# MCU_and_Peripherals.net
KiCad netlist of a schematic drawn in Altium Designer
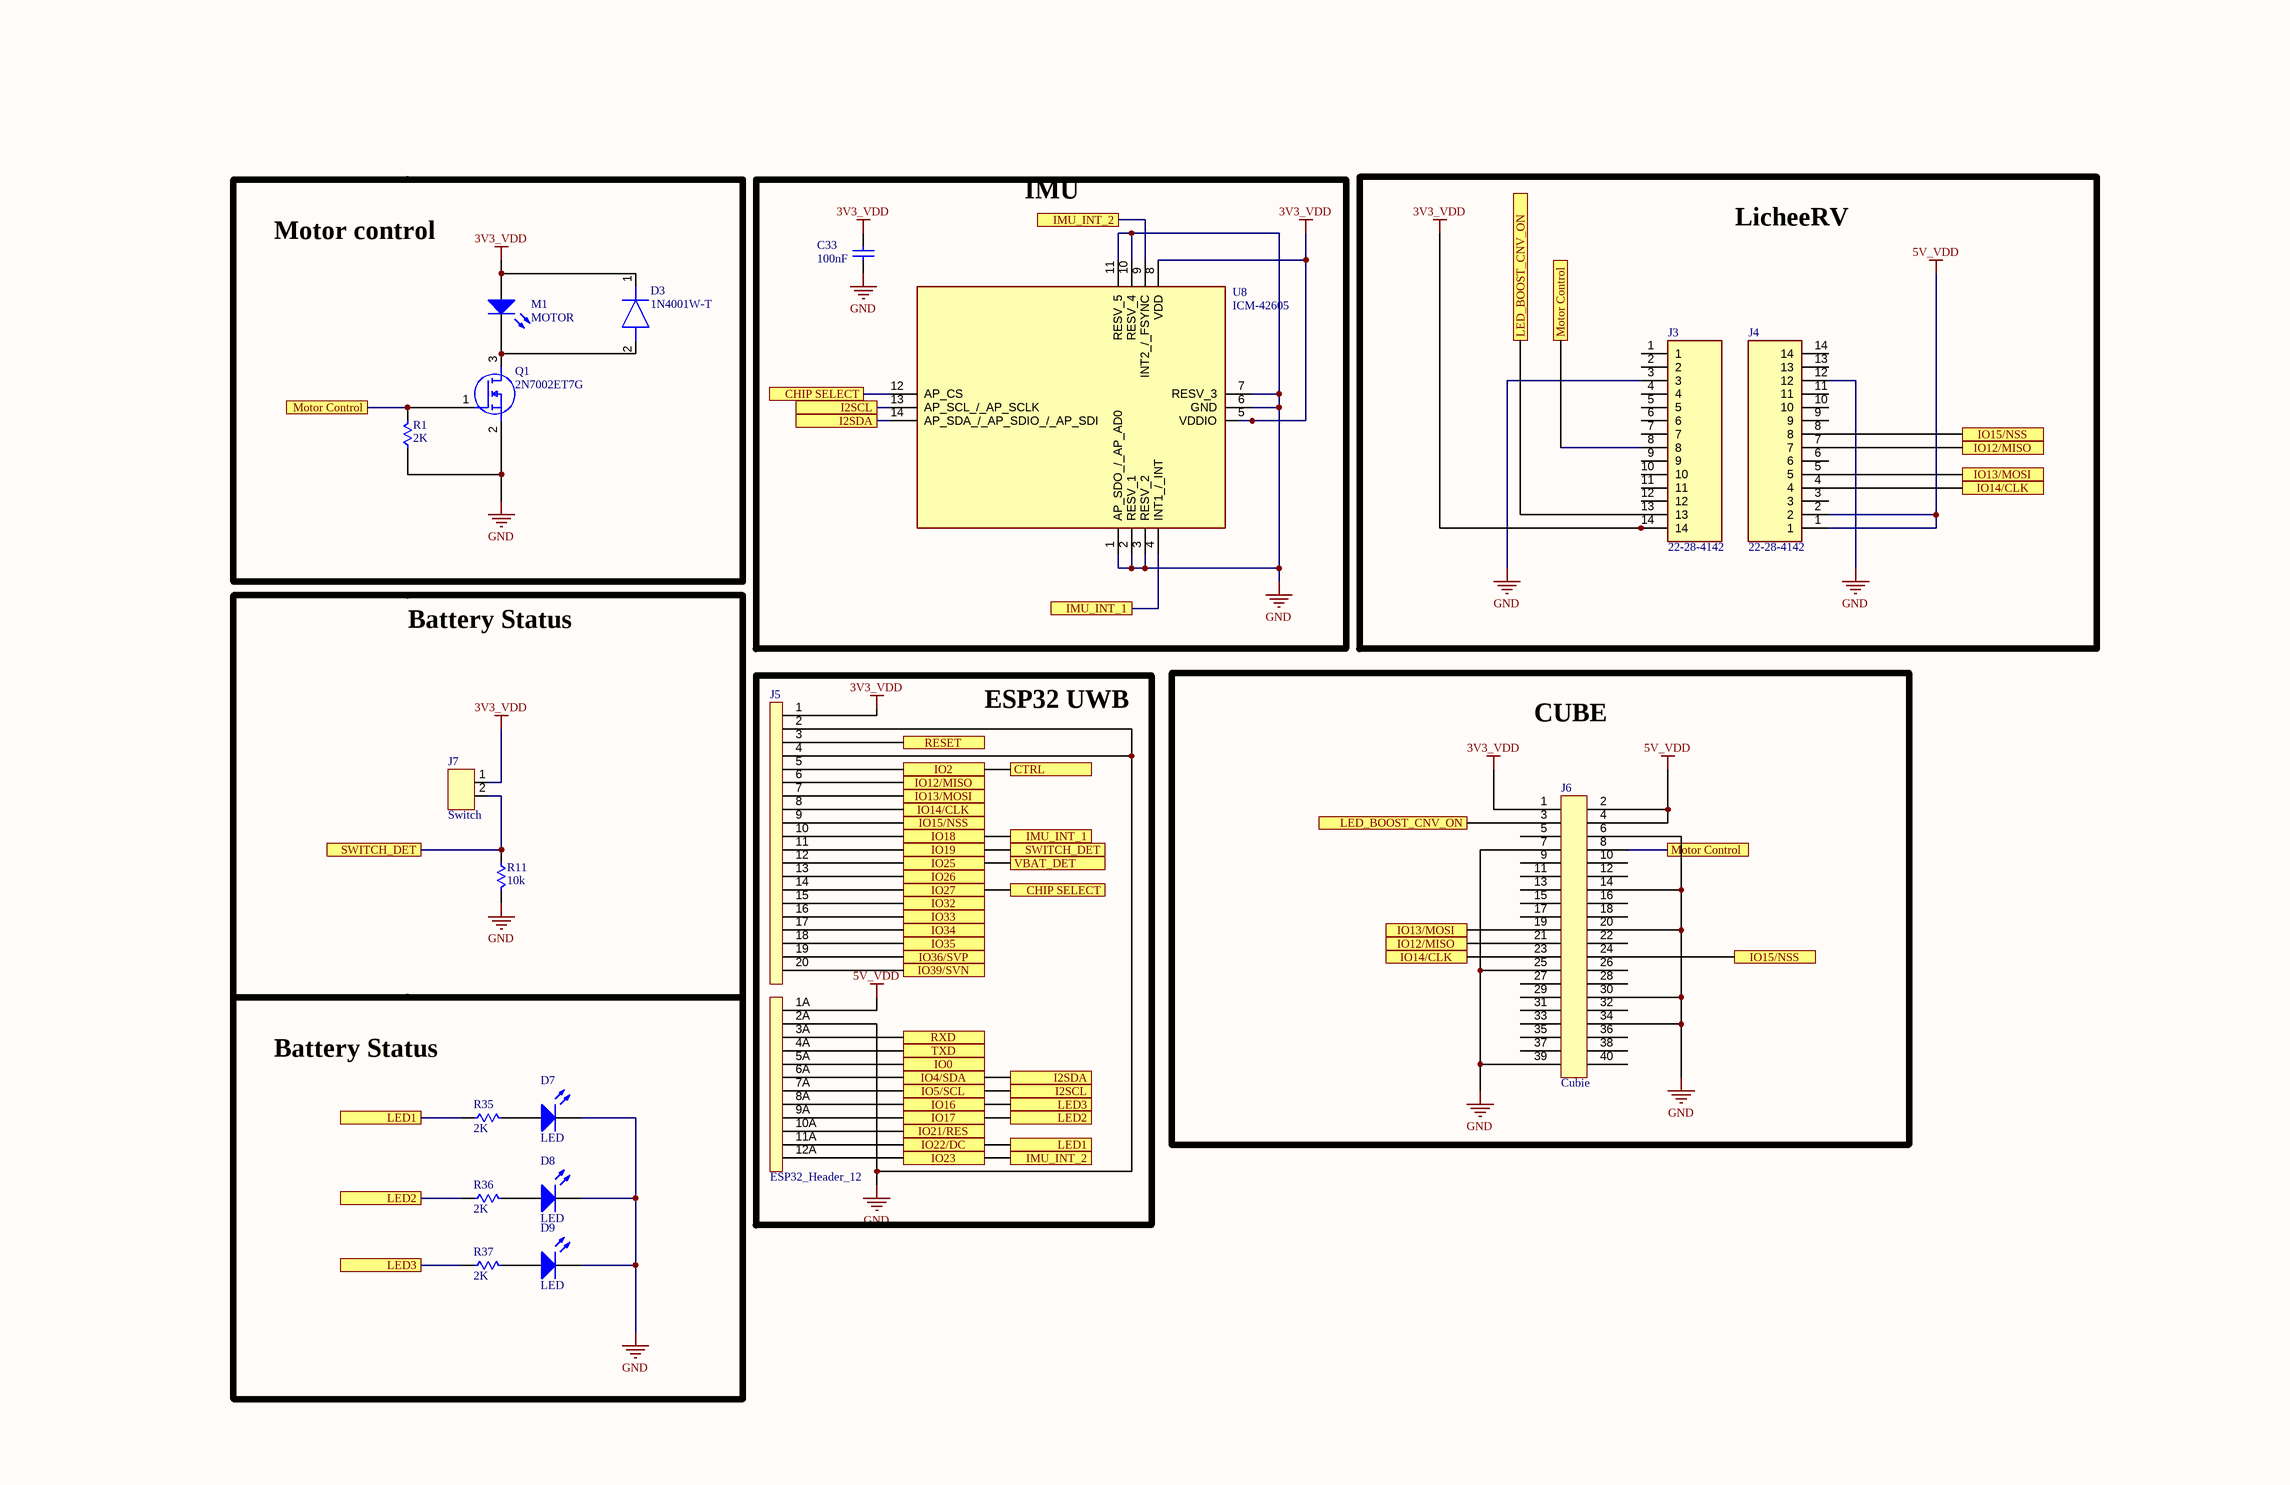
[diagram p0: MCU and Peripherals.SchDoc]

(export (version "E")
  (design (tool "Eeschema 10.0.6"))
  (components
    (comp (ref "C33")
      (value "Capacitor")
      (footprint "0603C")
      (description "Cap Ceramic 0.1uF 50VDC X7R 10% SMD 0603 Paper T/R")
      (fields
        (field (name "MANUFACTURER") "Samsung")
        (field (name "MANUFACTURER PART NUMBER") "CL10B104KB8NNNC")
        (field (name "CAPACITANCE") "100nF")
      )
      (libsource (lib "Altium_Library") (part "Capacitor"))
    )
    (comp (ref "D3")
      (value "1N4001W-T")
      (footprint "SODFL3818X130N")
      (description "Diode")
      (fields (field (name "MOUSER PART NUMBER") "583-1N4001W-T"))
      (libsource (lib "*") (part "1N4001W-T"))
    )
    (comp (ref "D7")
      (value "LED")
      (footprint "PcbLib1:SolderWires")
      (libsource (lib "Schlib1") (part "LED3"))
    )
    (comp (ref "D8")
      (value "LED")
      (footprint "PcbLib1:SolderWires")
      (libsource (lib "Schlib1") (part "LED3"))
    )
    (comp (ref "D9")
      (value "LED")
      (footprint "PcbLib1:SolderWires")
      (libsource (lib "Schlib1") (part "LED3"))
    )
    (comp (ref "J3")
      (value "22-28-4142")
      (footprint "PcbLib1:HDRV14W63P0X254_1X14_3556X250X950P")
      (description "Connector")
      (libsource (lib "*") (part "1-826629-4"))
    )
    (comp (ref "J4")
      (value "22-28-4142")
      (footprint "PcbLib1:HDRV14W63P0X254_1X14_3556X250X950P")
      (description "Connector")
      (libsource (lib "") (part "1-826629-4_1"))
    )
    (comp (ref "J5")
      (value "ESP32_Header_12")
      (footprint "12P-2.54")
      (libsource (lib "Schlib1") (part "ESP32_Header_12"))
    )
    (comp (ref "J6") (value "Cubie") (footprint "40Pin") (libsource (lib "Schlib1") (part "Cubie")))
    (comp (ref "J7") (value "Switch") (footprint "SWITCH SOLDER") (libsource (lib "Schlib1") (part "Switch")))
    (comp (ref "M1")
      (value "MOTOR")
      (footprint "PcbLib1:SolderWires")
      (description "LED")
      (libsource (lib "Schlib1") (part "LED3"))
    )
    (comp (ref "Q1")
      (value "2N7002ET7G")
      (footprint "PcbLib1:SOT96P237X111-3N")
      (description "MOSFET (N-Channel)")
      (fields (field (name "MOUSER PART NUMBER") "863-2N7002ET7G"))
      (libsource (lib "*") (part "2N7002ET7G"))
    )
    (comp (ref "R1")
      (value "2K")
      (footprint "PcbLib1:R0603")
      (description "RES SMD 2K OHM 1% 1/10W 0603")
      (fields
        (field (name "MANUFACTURER") "Yageo")
        (field (name "MANUFACTURER PART NUMBER") "RC0603FR-072KL")
      )
      (libsource (lib "Sunbull_V1R0") (part "RC0603FR-072KL"))
    )
    (comp (ref "R11")
      (value "10k")
      (footprint "PcbLib1:R0603")
      (fields
        (field (name "MANUFACTURER PART NUMBER") "RK73H1JTTD1002F")
        (field (name "TOLERANCE") "±1%")
        (field (name "MOUSER PART NUMBER") "603-RC0603FR-072KL")
      )
      (libsource (lib "Sunbull_V1R0") (part "RC0603FR-072KL"))
    )
    (comp (ref "R35")
      (value "2K")
      (footprint "PcbLib1:R0603")
      (description "RES SMD 2K OHM 1% 1/10W 0603")
      (fields
        (field (name "MANUFACTURER") "Yageo")
        (field (name "MANUFACTURER PART NUMBER") "RC0603FR-072KL")
      )
      (libsource (lib "Sunbull_V1R0") (part "RC0603FR-072KL"))
    )
    (comp (ref "R36")
      (value "2K")
      (footprint "PcbLib1:R0603")
      (description "RES SMD 2K OHM 1% 1/10W 0603")
      (fields
        (field (name "MANUFACTURER") "Yageo")
        (field (name "MANUFACTURER PART NUMBER") "RC0603FR-072KL")
      )
      (libsource (lib "Sunbull_V1R0") (part "RC0603FR-072KL"))
    )
    (comp (ref "R37")
      (value "2K")
      (footprint "PcbLib1:R0603")
      (description "RES SMD 2K OHM 1% 1/10W 0603")
      (fields
        (field (name "MANUFACTURER") "Yageo")
        (field (name "MANUFACTURER PART NUMBER") "RC0603FR-072KL")
      )
      (libsource (lib "Sunbull_V1R0") (part "RC0603FR-072KL"))
    )
    (comp (ref "U8")
      (value "ICM-42605")
      (footprint "PcbLib1:IIM42352")
      (description "Accelerometer")
      (fields (field (name "MOUSER PART NUMBER") "410-ICM-42605"))
      (libsource (lib "*") (part "ICM-42605"))
    )
  )
  (nets
    (net (code "1") (name "/CHIP SELECT") (class "Default")
      (node (ref "J5") (pin "14") (pintype "passive"))
      (node (ref "U8") (pin "12") (pinfunction "AP_CS_12") (pintype "passive"))
    )
    (net (code "2") (name "/CTRL") (class "Default") (node (ref "J5") (pin "5") (pintype "passive")))
    (net (code "3") (name "/I2SCL") (class "Default")
      (node (ref "J5") (pin "7A") (pintype "passive"))
      (node (ref "U8") (pin "13") (pinfunction "AP_SCL_/_AP_SCLK_13") (pintype "passive"))
    )
    (net (code "4") (name "/I2SDA") (class "Default")
      (node (ref "J5") (pin "6A") (pintype "passive"))
      (node (ref "U8") (pin "14") (pinfunction "AP_SDA_/_AP_SDIO_/_AP_SDI_14") (pintype "passive"))
    )
    (net (code "5") (name "/IMU_INT_1") (class "Default")
      (node (ref "J5") (pin "10") (pintype "passive"))
      (node (ref "U8") (pin "4") (pinfunction "INT1_/_INT_4") (pintype "passive"))
    )
    (net (code "6") (name "/IMU_INT_2") (class "Default")
      (node (ref "J5") (pin "12A") (pintype "passive"))
      (node (ref "U8") (pin "9") (pinfunction "INT2_/_FSYNC_9") (pintype "passive"))
    )
    (net (code "7") (name "/IO0") (class "Default") (node (ref "J5") (pin "5A") (pintype "passive")))
    (net (code "8") (name "/IO12{slash}MISO") (class "Default")
      (node (ref "J4") (pin "7") (pinfunction "7_7") (pintype "passive"))
      (node (ref "J5") (pin "6") (pintype "passive"))
      (node (ref "J6") (pin "21") (pinfunction "21_21") (pintype "passive"))
    )
    (net (code "9") (name "/IO13{slash}MOSI") (class "Default")
      (node (ref "J4") (pin "5") (pinfunction "5_5") (pintype "passive"))
      (node (ref "J5") (pin "7") (pintype "passive"))
      (node (ref "J6") (pin "19") (pinfunction "19_19") (pintype "passive"))
    )
    (net (code "10") (name "/IO14{slash}CLK") (class "Default")
      (node (ref "J4") (pin "4") (pinfunction "4_4") (pintype "passive"))
      (node (ref "J5") (pin "8") (pintype "passive"))
      (node (ref "J6") (pin "23") (pinfunction "23_23") (pintype "passive"))
    )
    (net (code "11") (name "/IO15{slash}NSS") (class "Default")
      (node (ref "J4") (pin "8") (pinfunction "8_8") (pintype "passive"))
      (node (ref "J5") (pin "9") (pintype "passive"))
      (node (ref "J6") (pin "24") (pinfunction "24_24") (pintype "passive"))
    )
    (net (code "12") (name "/IO16") (class "Default")
      (node (ref "J5") (pin "8A") (pintype "passive"))
      (node (ref "R37") (pin "1") (pinfunction "1_1") (pintype "passive"))
    )
    (net (code "13") (name "/IO17") (class "Default")
      (node (ref "J5") (pin "9A") (pintype "passive"))
      (node (ref "R36") (pin "1") (pinfunction "1_1") (pintype "passive"))
    )
    (net (code "14") (name "/IO19") (class "Default")
      (node (ref "J5") (pin "11") (pintype "passive"))
      (node (ref "J7") (pin "2") (pinfunction "2_2") (pintype "passive"))
      (node (ref "R11") (pin "1") (pinfunction "1_1") (pintype "passive"))
    )
    (net (code "15") (name "/IO21{slash}RES") (class "Default")
      (node (ref "J5") (pin "10A") (pintype "passive"))
    )
    (net (code "16") (name "/IO22{slash}DC") (class "Default")
      (node (ref "J5") (pin "11A") (pintype "passive"))
      (node (ref "R35") (pin "1") (pinfunction "1_1") (pintype "passive"))
    )
    (net (code "17") (name "/IO25") (class "Default") (node (ref "J5") (pin "12") (pintype "passive")))
    (net (code "18") (name "/IO26") (class "Default") (node (ref "J5") (pin "13") (pintype "passive")))
    (net (code "19") (name "/IO32") (class "Default") (node (ref "J5") (pin "15") (pintype "passive")))
    (net (code "20") (name "/IO33") (class "Default") (node (ref "J5") (pin "16") (pintype "passive")))
    (net (code "21") (name "/IO34") (class "Default") (node (ref "J5") (pin "17") (pintype "passive")))
    (net (code "22") (name "/IO35") (class "Default") (node (ref "J5") (pin "18") (pintype "passive")))
    (net (code "23") (name "/IO36{slash}SVP") (class "Default")
      (node (ref "J5") (pin "19") (pintype "passive"))
    )
    (net (code "24") (name "/IO39{slash}SVN") (class "Default")
      (node (ref "J5") (pin "20") (pintype "passive"))
    )
    (net (code "25") (name "/LED_BOOST_CNV_ON") (class "Default")
      (node (ref "J3") (pin "13") (pinfunction "13_13") (pintype "passive"))
      (node (ref "J6") (pin "3") (pinfunction "11_3") (pintype "passive"))
    )
    (net (code "26") (name "/Motor Control") (class "Default")
      (node (ref "J3") (pin "8") (pinfunction "8_8") (pintype "passive"))
      (node (ref "J6") (pin "8") (pinfunction "16_8") (pintype "passive"))
      (node (ref "Q1") (pin "1") (pinfunction "G_1") (pintype "passive"))
      (node (ref "R1") (pin "2") (pinfunction "2_2") (pintype "passive"))
    )
    (net (code "27") (name "/RESET") (class "Default") (node (ref "J5") (pin "3") (pintype "passive")))
    (net (code "28") (name "/RXD") (class "Default") (node (ref "J5") (pin "3A") (pintype "passive")))
    (net (code "29") (name "/TXD") (class "Default") (node (ref "J5") (pin "4A") (pintype "passive")))
    (net (code "30") (name "3V3_VDD") (class "Default")
      (node (ref "C33") (pin "2") (pinfunction "2_2") (pintype "passive"))
      (node (ref "D3") (pin "1") (pinfunction "K_1") (pintype "passive"))
      (node (ref "J3") (pin "14") (pinfunction "14_14") (pintype "passive"))
      (node (ref "J5") (pin "1") (pintype "passive"))
      (node (ref "J6") (pin "1") (pinfunction "9_1") (pintype "passive"))
      (node (ref "J7") (pin "1") (pinfunction "1_1") (pintype "passive"))
      (node (ref "M1") (pin "1") (pinfunction "A_1") (pintype "passive"))
      (node (ref "U8") (pin "5") (pinfunction "VDDIO_5") (pintype "passive"))
      (node (ref "U8") (pin "8") (pinfunction "VDD_8") (pintype "passive"))
    )
    (net (code "31") (name "5V_VDD") (class "Default")
      (node (ref "J4") (pin "1") (pinfunction "1_1") (pintype "passive"))
      (node (ref "J4") (pin "2") (pinfunction "2_2") (pintype "passive"))
      (node (ref "J5") (pin "1A") (pintype "passive"))
      (node (ref "J6") (pin "2") (pinfunction "10_2") (pintype "passive"))
      (node (ref "J6") (pin "4") (pinfunction "12_4") (pintype "passive"))
    )
    (net (code "32") (name "GND") (class "Default")
      (node (ref "C33") (pin "1") (pinfunction "1_1") (pintype "passive"))
      (node (ref "D7") (pin "2") (pinfunction "K_2") (pintype "passive"))
      (node (ref "D8") (pin "2") (pinfunction "K_2") (pintype "passive"))
      (node (ref "D9") (pin "2") (pinfunction "K_2") (pintype "passive"))
      (node (ref "J3") (pin "3") (pinfunction "3_3") (pintype "passive"))
      (node (ref "J4") (pin "12") (pinfunction "12_12") (pintype "passive"))
      (node (ref "J5") (pin "2") (pintype "passive"))
      (node (ref "J5") (pin "2A") (pintype "passive"))
      (node (ref "J5") (pin "4") (pintype "passive"))
      (node (ref "J6") (pin "14") (pinfunction "22_14") (pintype "passive"))
      (node (ref "J6") (pin "20") (pinfunction "20_20") (pintype "passive"))
      (node (ref "J6") (pin "25") (pinfunction "25_25") (pintype "passive"))
      (node (ref "J6") (pin "30") (pinfunction "30_30") (pintype "passive"))
      (node (ref "J6") (pin "34") (pinfunction "34_34") (pintype "passive"))
      (node (ref "J6") (pin "39") (pinfunction "39_39") (pintype "passive"))
      (node (ref "J6") (pin "6") (pinfunction "14_6") (pintype "passive"))
      (node (ref "J6") (pin "7") (pinfunction "15_7") (pintype "passive"))
      (node (ref "Q1") (pin "2") (pinfunction "S_2") (pintype "passive"))
      (node (ref "R1") (pin "1") (pinfunction "1_1") (pintype "passive"))
      (node (ref "R11") (pin "2") (pinfunction "2_2") (pintype "passive"))
      (node (ref "U8") (pin "1") (pinfunction "AP_SDO_/_AP_AD0_1") (pintype "passive"))
      (node (ref "U8") (pin "10") (pinfunction "RESV_4_10") (pintype "passive"))
      (node (ref "U8") (pin "11") (pinfunction "RESV_5_11") (pintype "passive"))
      (node (ref "U8") (pin "2") (pinfunction "RESV_1_2") (pintype "passive"))
      (node (ref "U8") (pin "3") (pinfunction "RESV_2_3") (pintype "passive"))
      (node (ref "U8") (pin "6") (pinfunction "GND_6") (pintype "passive"))
      (node (ref "U8") (pin "7") (pinfunction "RESV_3_7") (pintype "passive"))
    )
    (net (code "33") (name "Net-(D3-A)") (class "Default")
      (node (ref "D3") (pin "2") (pinfunction "A_2") (pintype "passive"))
      (node (ref "M1") (pin "2") (pinfunction "K_2") (pintype "passive"))
      (node (ref "Q1") (pin "3") (pinfunction "D_3") (pintype "passive"))
    )
    (net (code "34") (name "Net-(D7-A)") (class "Default")
      (node (ref "D7") (pin "1") (pinfunction "A_1") (pintype "passive"))
      (node (ref "R35") (pin "2") (pinfunction "2_2") (pintype "passive"))
    )
    (net (code "35") (name "Net-(D8-A)") (class "Default")
      (node (ref "D8") (pin "1") (pinfunction "A_1") (pintype "passive"))
      (node (ref "R36") (pin "2") (pinfunction "2_2") (pintype "passive"))
    )
    (net (code "36") (name "Net-(D9-A)") (class "Default")
      (node (ref "D9") (pin "1") (pinfunction "A_1") (pintype "passive"))
      (node (ref "R37") (pin "2") (pinfunction "2_2") (pintype "passive"))
    )
    (net (code "37") (name "unconnected-(J3-Pad1)") (class "Default")
      (node (ref "J3") (pin "1") (pinfunction "1_1") (pintype "passive"))
    )
    (net (code "38") (name "unconnected-(J3-Pad2)") (class "Default")
      (node (ref "J3") (pin "2") (pinfunction "2_2") (pintype "passive"))
    )
    (net (code "39") (name "unconnected-(J3-Pad4)") (class "Default")
      (node (ref "J3") (pin "4") (pinfunction "4_4") (pintype "passive"))
    )
    (net (code "40") (name "unconnected-(J3-Pad5)") (class "Default")
      (node (ref "J3") (pin "5") (pinfunction "5_5") (pintype "passive"))
    )
    (net (code "41") (name "unconnected-(J3-Pad6)") (class "Default")
      (node (ref "J3") (pin "6") (pinfunction "6_6") (pintype "passive"))
    )
    (net (code "42") (name "unconnected-(J3-Pad7)") (class "Default")
      (node (ref "J3") (pin "7") (pinfunction "7_7") (pintype "passive"))
    )
    (net (code "43") (name "unconnected-(J3-Pad9)") (class "Default")
      (node (ref "J3") (pin "9") (pinfunction "9_9") (pintype "passive"))
    )
    (net (code "44") (name "unconnected-(J3-Pad10)") (class "Default")
      (node (ref "J3") (pin "10") (pinfunction "10_10") (pintype "passive"))
    )
    (net (code "45") (name "unconnected-(J3-Pad11)") (class "Default")
      (node (ref "J3") (pin "11") (pinfunction "11_11") (pintype "passive"))
    )
    (net (code "46") (name "unconnected-(J3-Pad12)") (class "Default")
      (node (ref "J3") (pin "12") (pinfunction "12_12") (pintype "passive"))
    )
    (net (code "47") (name "unconnected-(J4-Pad3)") (class "Default")
      (node (ref "J4") (pin "3") (pinfunction "3_3") (pintype "passive"))
    )
    (net (code "48") (name "unconnected-(J4-Pad6)") (class "Default")
      (node (ref "J4") (pin "6") (pinfunction "6_6") (pintype "passive"))
    )
    (net (code "49") (name "unconnected-(J4-Pad9)") (class "Default")
      (node (ref "J4") (pin "9") (pinfunction "9_9") (pintype "passive"))
    )
    (net (code "50") (name "unconnected-(J4-Pad10)") (class "Default")
      (node (ref "J4") (pin "10") (pinfunction "10_10") (pintype "passive"))
    )
    (net (code "51") (name "unconnected-(J4-Pad11)") (class "Default")
      (node (ref "J4") (pin "11") (pinfunction "11_11") (pintype "passive"))
    )
    (net (code "52") (name "unconnected-(J4-Pad13)") (class "Default")
      (node (ref "J4") (pin "13") (pinfunction "13_13") (pintype "passive"))
    )
    (net (code "53") (name "unconnected-(J4-Pad14)") (class "Default")
      (node (ref "J4") (pin "14") (pinfunction "14_14") (pintype "passive"))
    )
    (net (code "54") (name "unconnected-(J6-13-Pad5)") (class "Default")
      (node (ref "J6") (pin "5") (pinfunction "13_5") (pintype "passive"))
    )
    (net (code "55") (name "unconnected-(J6-17-Pad9)") (class "Default")
      (node (ref "J6") (pin "9") (pinfunction "17_9") (pintype "passive"))
    )
    (net (code "56") (name "unconnected-(J6-18-Pad10)") (class "Default")
      (node (ref "J6") (pin "10") (pinfunction "18_10") (pintype "passive"))
    )
    (net (code "57") (name "unconnected-(J6-19-Pad11)") (class "Default")
      (node (ref "J6") (pin "11") (pinfunction "19_11") (pintype "passive"))
    )
    (net (code "58") (name "unconnected-(J6-20-Pad12)") (class "Default")
      (node (ref "J6") (pin "12") (pinfunction "20_12") (pintype "passive"))
    )
    (net (code "59") (name "unconnected-(J6-21-Pad13)") (class "Default")
      (node (ref "J6") (pin "13") (pinfunction "21_13") (pintype "passive"))
    )
    (net (code "60") (name "unconnected-(J6-23-Pad15)") (class "Default")
      (node (ref "J6") (pin "15") (pinfunction "23_15") (pintype "passive"))
    )
    (net (code "61") (name "unconnected-(J6-24-Pad16)") (class "Default")
      (node (ref "J6") (pin "16") (pinfunction "24_16") (pintype "passive"))
    )
    (net (code "62") (name "unconnected-(J6-Pad17)") (class "Default")
      (node (ref "J6") (pin "17") (pinfunction "17_17") (pintype "passive"))
    )
    (net (code "63") (name "unconnected-(J6-Pad18)") (class "Default")
      (node (ref "J6") (pin "18") (pinfunction "18_18") (pintype "passive"))
    )
    (net (code "64") (name "unconnected-(J6-Pad22)") (class "Default")
      (node (ref "J6") (pin "22") (pinfunction "22_22") (pintype "passive"))
    )
    (net (code "65") (name "unconnected-(J6-Pad26)") (class "Default")
      (node (ref "J6") (pin "26") (pinfunction "26_26") (pintype "passive"))
    )
    (net (code "66") (name "unconnected-(J6-Pad27)") (class "Default")
      (node (ref "J6") (pin "27") (pinfunction "27_27") (pintype "passive"))
    )
    (net (code "67") (name "unconnected-(J6-Pad28)") (class "Default")
      (node (ref "J6") (pin "28") (pinfunction "28_28") (pintype "passive"))
    )
    (net (code "68") (name "unconnected-(J6-Pad29)") (class "Default")
      (node (ref "J6") (pin "29") (pinfunction "29_29") (pintype "passive"))
    )
    (net (code "69") (name "unconnected-(J6-Pad31)") (class "Default")
      (node (ref "J6") (pin "31") (pinfunction "31_31") (pintype "passive"))
    )
    (net (code "70") (name "unconnected-(J6-Pad32)") (class "Default")
      (node (ref "J6") (pin "32") (pinfunction "32_32") (pintype "passive"))
    )
    (net (code "71") (name "unconnected-(J6-Pad33)") (class "Default")
      (node (ref "J6") (pin "33") (pinfunction "33_33") (pintype "passive"))
    )
    (net (code "72") (name "unconnected-(J6-Pad35)") (class "Default")
      (node (ref "J6") (pin "35") (pinfunction "35_35") (pintype "passive"))
    )
    (net (code "73") (name "unconnected-(J6-Pad36)") (class "Default")
      (node (ref "J6") (pin "36") (pinfunction "36_36") (pintype "passive"))
    )
    (net (code "74") (name "unconnected-(J6-Pad37)") (class "Default")
      (node (ref "J6") (pin "37") (pinfunction "37_37") (pintype "passive"))
    )
    (net (code "75") (name "unconnected-(J6-Pad38)") (class "Default")
      (node (ref "J6") (pin "38") (pinfunction "38_38") (pintype "passive"))
    )
    (net (code "76") (name "unconnected-(J6-Pad40)") (class "Default")
      (node (ref "J6") (pin "40") (pinfunction "40_40") (pintype "passive"))
    )
  )
)
